# Baro.net
KiCad netlist of a schematic drawn in Altium Designer
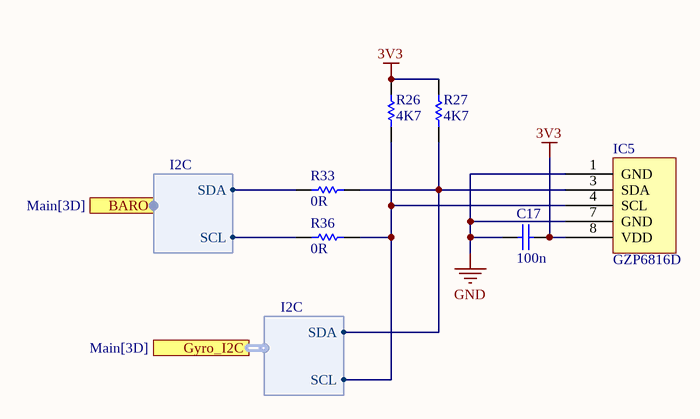
[diagram p0: Baro.SchDoc]

(export (version "E")
  (design (tool "Eeschema 10.0.6"))
  (components
    (comp (ref "C17")
      (value "100n")
      (footprint "CAPC0603(1608)55_N")
      (description "Keramikvielschichtkondensator, SMD, Baureihe MC, ± 20%")
      (fields (field (name "MANUFACTURER") "Multicomp"))
      (libsource (lib "Standardbauteile") (part "Cap 100n"))
    )
    (comp (ref "IC5")
      (value "GZP6816D")
      (footprint "GZP6816D")
      (libsource (lib "Custom Components") (part "GZP6816D"))
    )
    (comp (ref "R26")
      (value "4K7")
      (footprint "RESC0603(1608)_N")
      (description "Chipwiderstand, SMD, Baureihe MC, 5%")
      (fields (field (name "MANUFACTURER") "Multicomp"))
      (libsource (lib "Standardbauteile") (part "Res 4k7"))
    )
    (comp (ref "R27")
      (value "4K7")
      (footprint "RESC0603(1608)_N")
      (description "Chipwiderstand, SMD, Baureihe MC, 5%")
      (fields (field (name "MANUFACTURER") "Multicomp"))
      (libsource (lib "Standardbauteile") (part "Res 4k7"))
    )
    (comp (ref "R33")
      (value "0R")
      (footprint "RESC1005X40X25NL05T10")
      (fields (field (name "MANUFACTURER") "Yageo / Phycomp") (field (name "PART NUMBER") "RC0402JR-070RL"))
      (libsource (lib "Altium Content Vault") (part "RES"))
    )
    (comp (ref "R36")
      (value "0R")
      (footprint "RESC1005X40X25NL05T10")
      (fields (field (name "MANUFACTURER") "Yageo / Phycomp") (field (name "PART NUMBER") "RC0402JR-070RL"))
      (libsource (lib "Altium Content Vault") (part "RES"))
    )
  )
  (nets
    (net (code "3") (name "3V3") (class "Default")
      (node (ref "C17") (pin "1") (pinfunction "1_1") (pintype "passive"))
      (node (ref "IC5") (pin "8") (pinfunction "VDD_8") (pintype "passive"))
      (node (ref "R26") (pin "2") (pinfunction "2_2") (pintype "passive"))
      (node (ref "R27") (pin "2") (pinfunction "2_2") (pintype "passive"))
    )
    (net (code "4") (name "GND") (class "Default")
      (node (ref "C17") (pin "2") (pinfunction "2_2") (pintype "passive"))
      (node (ref "IC5") (pin "1") (pinfunction "GND_1") (pintype "passive"))
      (node (ref "IC5") (pin "7") (pinfunction "GND_7") (pintype "passive"))
    )
    (net (code "5") (name "Net-(IC5-SCL)") (class "Default")
      (node (ref "IC5") (pin "4") (pinfunction "SCL_4") (pintype "passive"))
      (node (ref "R26") (pin "1") (pinfunction "1_1") (pintype "passive"))
      (node (ref "R36") (pin "2") (pinfunction "2_2") (pintype "passive"))
    )
    (net (code "6") (name "Net-(IC5-SDA)") (class "Default")
      (node (ref "IC5") (pin "3") (pinfunction "SDA_3") (pintype "passive"))
      (node (ref "R27") (pin "1") (pinfunction "1_1") (pintype "passive"))
      (node (ref "R33") (pin "2") (pinfunction "2_2") (pintype "passive"))
    )
    (net (code "7") (name "unconnected-(R33-Pad1)") (class "Default")
      (node (ref "R33") (pin "1") (pinfunction "1_1") (pintype "passive"))
    )
    (net (code "8") (name "unconnected-(R36-Pad1)") (class "Default")
      (node (ref "R36") (pin "1") (pinfunction "1_1") (pintype "passive"))
    )
  )
)
